# Blackberry_Trackballer_Breakout.net
KiCad netlist of a schematic drawn in EAGLE
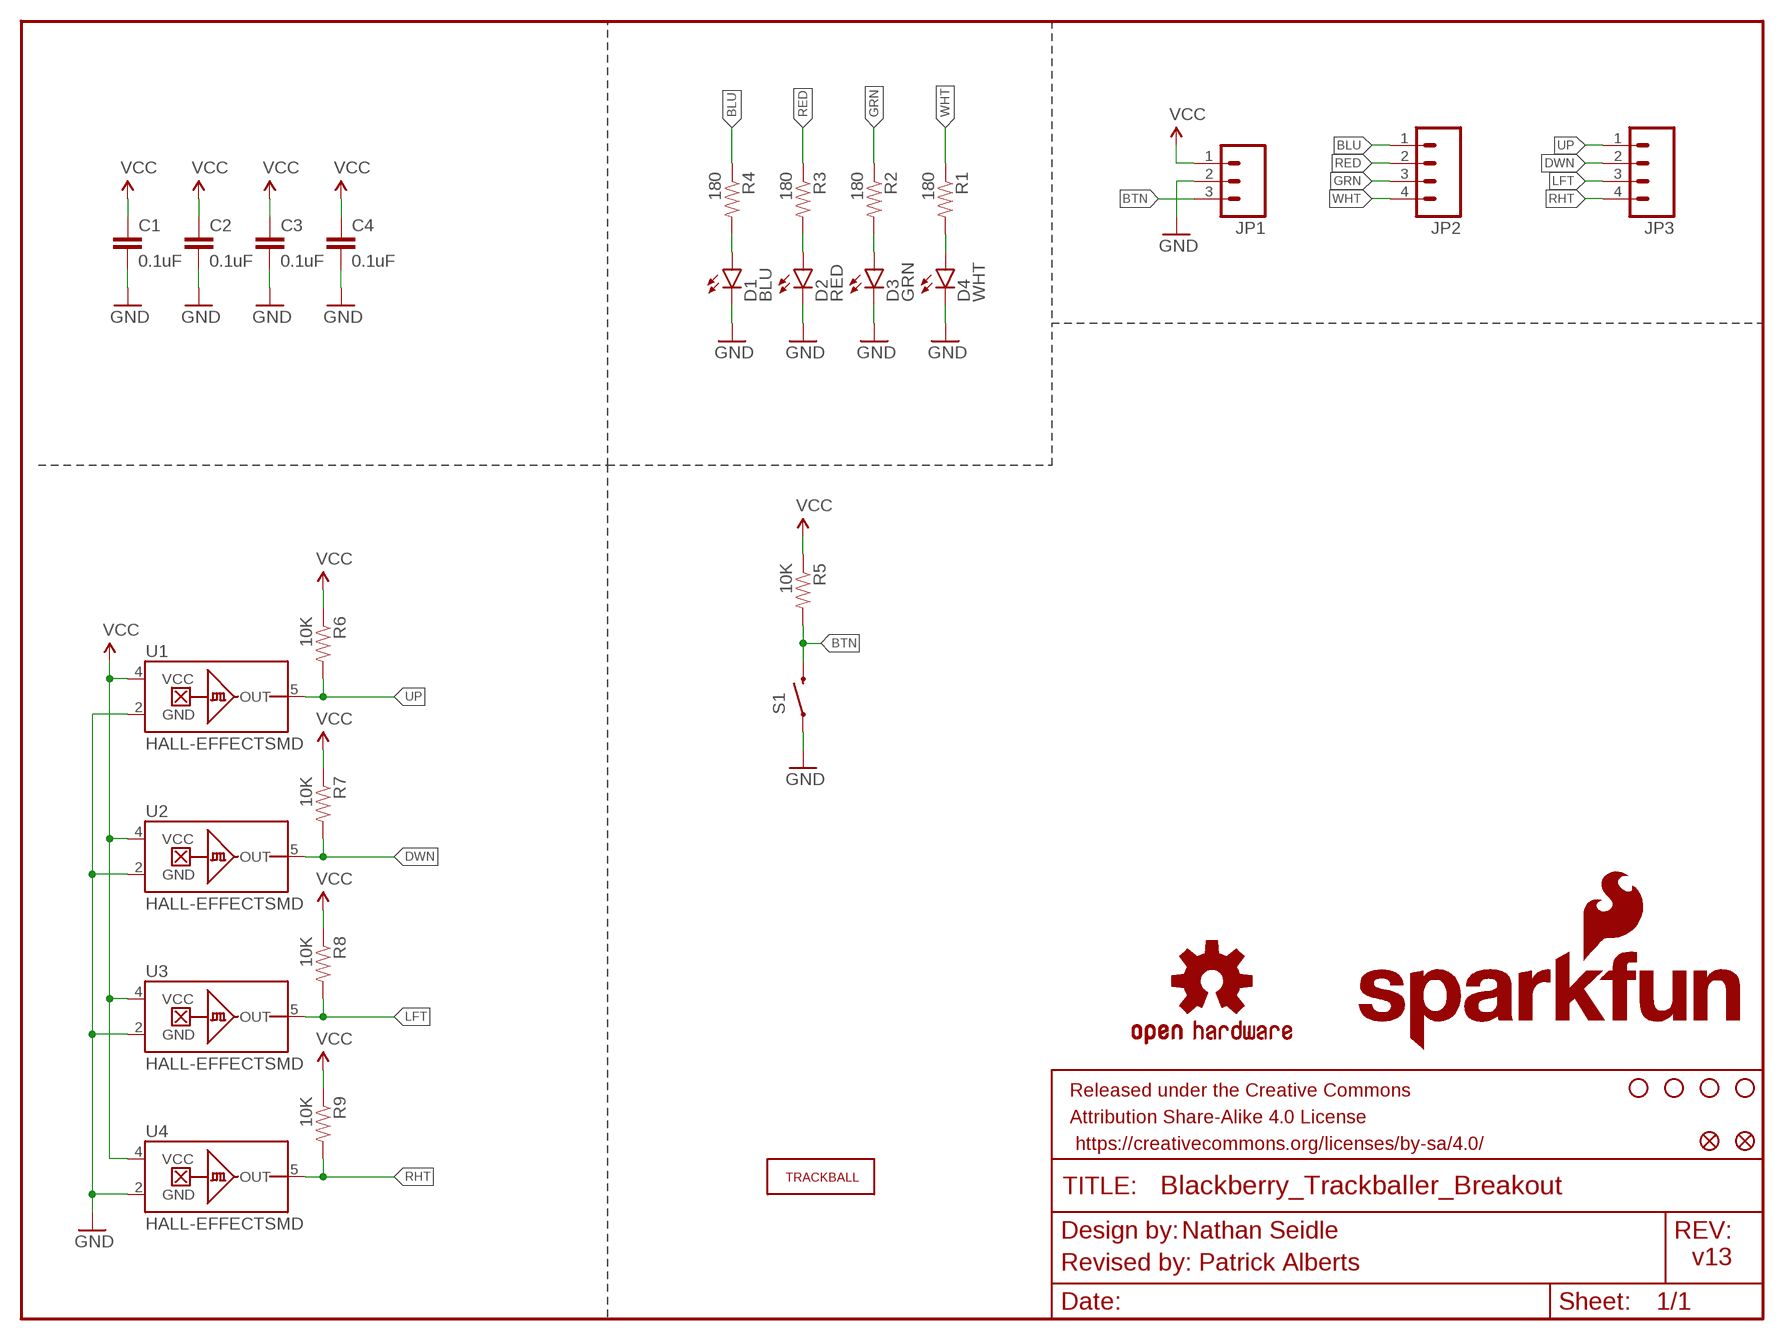
[diagram p0: schematic, sheet 1]

(export (version "E")
  (design (tool "Eeschema 10.0.6"))
  (components
    (comp (ref "C1")
      (value "0.1uF")
      (footprint "eagle-import:0603-CAP")
      (libsource (lib "eagle-import") (part "0.1UF-25V(+80/-20%)(0603)"))
    )
    (comp (ref "C2")
      (value "0.1uF")
      (footprint "eagle-import:0603-CAP")
      (libsource (lib "eagle-import") (part "0.1UF-25V(+80/-20%)(0603)"))
    )
    (comp (ref "C3")
      (value "0.1uF")
      (footprint "eagle-import:0603-CAP")
      (libsource (lib "eagle-import") (part "0.1UF-25V(+80/-20%)(0603)"))
    )
    (comp (ref "C4")
      (value "0.1uF")
      (footprint "eagle-import:0603-CAP")
      (libsource (lib "eagle-import") (part "0.1UF-25V(+80/-20%)(0603)"))
    )
    (comp (ref "D1")
      (value "BLU")
      (footprint "eagle-import:LED-0603")
      (libsource (lib "eagle-import") (part "LED-BLUE0603"))
    )
    (comp (ref "D2")
      (value "RED")
      (footprint "eagle-import:LED-0603")
      (libsource (lib "eagle-import") (part "LED-RED0603"))
    )
    (comp (ref "D3")
      (value "GRN")
      (footprint "eagle-import:LED-0603")
      (libsource (lib "eagle-import") (part "LED-GREEN0603"))
    )
    (comp (ref "D4")
      (value "WHT")
      (footprint "eagle-import:LED-0603")
      (libsource (lib "eagle-import") (part "LED-WHITE0603"))
    )
    (comp (ref "E$1")
      (value "FIDUCIAL1X2")
      (footprint "eagle-import:FIDUCIAL-1X2")
      (libsource (lib "eagle-import") (part "FIDUCIAL1X2"))
    )
    (comp (ref "E$2")
      (value "FIDUCIAL1X2")
      (footprint "eagle-import:FIDUCIAL-1X2")
      (libsource (lib "eagle-import") (part "FIDUCIAL1X2"))
    )
    (comp (ref "FRAME1")
      (value "FRAME-LETTER")
      (footprint "eagle-import:CREATIVE_COMMONS")
      (libsource (lib "eagle-import") (part "FRAME-LETTER"))
    )
    (comp (ref "JP1")
      (value "M03PTH")
      (footprint "eagle-import:1X03")
      (libsource (lib "eagle-import") (part "M03PTH"))
    )
    (comp (ref "JP2")
      (value "M04PTH")
      (footprint "eagle-import:1X04")
      (libsource (lib "eagle-import") (part "M04PTH"))
    )
    (comp (ref "JP3")
      (value "M04PTH")
      (footprint "eagle-import:1X04")
      (libsource (lib "eagle-import") (part "M04PTH"))
    )
    (comp (ref "LOGO1")
      (value "SFE_LOGO_NAME_FLAME.2_INCH")
      (footprint "eagle-import:SFE_LOGO_NAME_FLAME_.2")
      (libsource (lib "eagle-import") (part "SFE_LOGO_NAME_FLAME.2_INCH"))
    )
    (comp (ref "LOGO2")
      (value "OSHW-LOGOS")
      (footprint "eagle-import:OSHW-LOGO-S")
      (libsource (lib "eagle-import") (part "OSHW-LOGOS"))
    )
    (comp (ref "R1")
      (value "180")
      (footprint "eagle-import:0603-RES")
      (libsource (lib "eagle-import") (part "180OHM1/10W1%(0603)"))
    )
    (comp (ref "R2")
      (value "180")
      (footprint "eagle-import:0603-RES")
      (libsource (lib "eagle-import") (part "180OHM1/10W1%(0603)"))
    )
    (comp (ref "R3")
      (value "180")
      (footprint "eagle-import:0603-RES")
      (libsource (lib "eagle-import") (part "180OHM1/10W1%(0603)"))
    )
    (comp (ref "R4")
      (value "180")
      (footprint "eagle-import:0603-RES")
      (libsource (lib "eagle-import") (part "180OHM1/10W1%(0603)"))
    )
    (comp (ref "R5")
      (value "10K")
      (footprint "eagle-import:0603-RES")
      (libsource (lib "eagle-import") (part "10KOHM1/10W1%(0603)0603"))
    )
    (comp (ref "R6")
      (value "10K")
      (footprint "eagle-import:0603-RES")
      (libsource (lib "eagle-import") (part "10KOHM1/10W1%(0603)0603"))
    )
    (comp (ref "R7")
      (value "10K")
      (footprint "eagle-import:0603-RES")
      (libsource (lib "eagle-import") (part "10KOHM1/10W1%(0603)0603"))
    )
    (comp (ref "R8")
      (value "10K")
      (footprint "eagle-import:0603-RES")
      (libsource (lib "eagle-import") (part "10KOHM1/10W1%(0603)0603"))
    )
    (comp (ref "R9")
      (value "10K")
      (footprint "eagle-import:0603-RES")
      (libsource (lib "eagle-import") (part "10KOHM1/10W1%(0603)0603"))
    )
    (comp (ref "S1")
      (value "SWITCH-MOMENTARY-2SMD-2")
      (footprint "eagle-import:TACTILE_SWITCH_SMD-2")
      (libsource (lib "eagle-import") (part "SWITCH-MOMENTARY-2SMD-2"))
    )
    (comp (ref "U$1")
      (value "STAND-OFF")
      (footprint "eagle-import:STAND-OFF")
      (libsource (lib "eagle-import") (part "STAND-OFF"))
    )
    (comp (ref "U$3")
      (value "TRACKBALLMECH")
      (footprint "eagle-import:TRACKBALL")
      (libsource (lib "eagle-import") (part "TRACKBALLMECH"))
    )
    (comp (ref "U$8")
      (value "STAND-OFF")
      (footprint "eagle-import:STAND-OFF")
      (libsource (lib "eagle-import") (part "STAND-OFF"))
    )
    (comp (ref "U$11")
      (value "STAND-OFF")
      (footprint "eagle-import:STAND-OFF")
      (libsource (lib "eagle-import") (part "STAND-OFF"))
    )
    (comp (ref "U$14")
      (value "STAND-OFF")
      (footprint "eagle-import:STAND-OFF")
      (libsource (lib "eagle-import") (part "STAND-OFF"))
    )
    (comp (ref "U1")
      (value "HALL-EFFECTSMD")
      (footprint "eagle-import:SC70")
      (libsource (lib "eagle-import") (part "HALL-EFFECTSMD"))
    )
    (comp (ref "U2")
      (value "HALL-EFFECTSMD")
      (footprint "eagle-import:SC70")
      (libsource (lib "eagle-import") (part "HALL-EFFECTSMD"))
    )
    (comp (ref "U3")
      (value "HALL-EFFECTSMD")
      (footprint "eagle-import:SC70")
      (libsource (lib "eagle-import") (part "HALL-EFFECTSMD"))
    )
    (comp (ref "U4")
      (value "HALL-EFFECTSMD")
      (footprint "eagle-import:SC70")
      (libsource (lib "eagle-import") (part "HALL-EFFECTSMD"))
    )
  )
  (nets
    (net (code "1") (name "BLU") (class "Default")
      (node (ref "JP2") (pin "1") (pinfunction "1_1") (pintype "passive"))
      (node (ref "R4") (pin "1") (pinfunction "1_1") (pintype "passive"))
    )
    (net (code "2") (name "BTN") (class "Default")
      (node (ref "JP1") (pin "3") (pinfunction "3_3") (pintype "passive"))
      (node (ref "R5") (pin "2") (pinfunction "2_2") (pintype "passive"))
      (node (ref "S1") (pin "1") (pinfunction "2_1") (pintype "passive"))
    )
    (net (code "3") (name "DWN") (class "Default")
      (node (ref "JP3") (pin "2") (pinfunction "2_2") (pintype "passive"))
      (node (ref "R7") (pin "2") (pinfunction "2_2") (pintype "passive"))
      (node (ref "U2") (pin "5") (pinfunction "OUT_5") (pintype "bidirectional"))
    )
    (net (code "4") (name "GND") (class "Default")
      (node (ref "C1") (pin "2") (pinfunction "2_2") (pintype "passive"))
      (node (ref "C2") (pin "2") (pinfunction "2_2") (pintype "passive"))
      (node (ref "C3") (pin "2") (pinfunction "2_2") (pintype "passive"))
      (node (ref "C4") (pin "2") (pinfunction "2_2") (pintype "passive"))
      (node (ref "D1") (pin "C") (pinfunction "C_C") (pintype "passive"))
      (node (ref "D2") (pin "C") (pinfunction "C_C") (pintype "passive"))
      (node (ref "D3") (pin "C") (pinfunction "C_C") (pintype "passive"))
      (node (ref "D4") (pin "C") (pinfunction "C_C") (pintype "passive"))
      (node (ref "JP1") (pin "2") (pinfunction "2_2") (pintype "passive"))
      (node (ref "S1") (pin "2") (pinfunction "1_2") (pintype "passive"))
      (node (ref "U1") (pin "2") (pinfunction "GND_2") (pintype "bidirectional"))
      (node (ref "U2") (pin "2") (pinfunction "GND_2") (pintype "bidirectional"))
      (node (ref "U3") (pin "2") (pinfunction "GND_2") (pintype "bidirectional"))
      (node (ref "U4") (pin "2") (pinfunction "GND_2") (pintype "bidirectional"))
    )
    (net (code "5") (name "GRN") (class "Default")
      (node (ref "JP2") (pin "3") (pinfunction "3_3") (pintype "passive"))
      (node (ref "R2") (pin "1") (pinfunction "1_1") (pintype "passive"))
    )
    (net (code "6") (name "LFT") (class "Default")
      (node (ref "JP3") (pin "3") (pinfunction "3_3") (pintype "passive"))
      (node (ref "R8") (pin "2") (pinfunction "2_2") (pintype "passive"))
      (node (ref "U3") (pin "5") (pinfunction "OUT_5") (pintype "bidirectional"))
    )
    (net (code "7") (name "Net-(D1-PadA)") (class "Default")
      (node (ref "D1") (pin "A") (pinfunction "A_A") (pintype "passive"))
      (node (ref "R4") (pin "2") (pinfunction "2_2") (pintype "passive"))
    )
    (net (code "8") (name "Net-(D2-PadA)") (class "Default")
      (node (ref "D2") (pin "A") (pinfunction "A_A") (pintype "passive"))
      (node (ref "R3") (pin "2") (pinfunction "2_2") (pintype "passive"))
    )
    (net (code "9") (name "Net-(D3-PadA)") (class "Default")
      (node (ref "D3") (pin "A") (pinfunction "A_A") (pintype "passive"))
      (node (ref "R2") (pin "2") (pinfunction "2_2") (pintype "passive"))
    )
    (net (code "10") (name "Net-(D4-PadA)") (class "Default")
      (node (ref "D4") (pin "A") (pinfunction "A_A") (pintype "passive"))
      (node (ref "R1") (pin "2") (pinfunction "2_2") (pintype "passive"))
    )
    (net (code "11") (name "RED") (class "Default")
      (node (ref "JP2") (pin "2") (pinfunction "2_2") (pintype "passive"))
      (node (ref "R3") (pin "1") (pinfunction "1_1") (pintype "passive"))
    )
    (net (code "12") (name "RHT") (class "Default")
      (node (ref "JP3") (pin "4") (pinfunction "4_4") (pintype "passive"))
      (node (ref "R9") (pin "2") (pinfunction "2_2") (pintype "passive"))
      (node (ref "U4") (pin "5") (pinfunction "OUT_5") (pintype "bidirectional"))
    )
    (net (code "13") (name "UP") (class "Default")
      (node (ref "JP3") (pin "1") (pinfunction "1_1") (pintype "passive"))
      (node (ref "R6") (pin "2") (pinfunction "2_2") (pintype "passive"))
      (node (ref "U1") (pin "5") (pinfunction "OUT_5") (pintype "bidirectional"))
    )
    (net (code "14") (name "VCC") (class "Default")
      (node (ref "C1") (pin "1") (pinfunction "1_1") (pintype "passive"))
      (node (ref "C2") (pin "1") (pinfunction "1_1") (pintype "passive"))
      (node (ref "C3") (pin "1") (pinfunction "1_1") (pintype "passive"))
      (node (ref "C4") (pin "1") (pinfunction "1_1") (pintype "passive"))
      (node (ref "JP1") (pin "1") (pinfunction "1_1") (pintype "passive"))
      (node (ref "R5") (pin "1") (pinfunction "1_1") (pintype "passive"))
      (node (ref "R6") (pin "1") (pinfunction "1_1") (pintype "passive"))
      (node (ref "R7") (pin "1") (pinfunction "1_1") (pintype "passive"))
      (node (ref "R8") (pin "1") (pinfunction "1_1") (pintype "passive"))
      (node (ref "R9") (pin "1") (pinfunction "1_1") (pintype "passive"))
      (node (ref "U1") (pin "4") (pinfunction "VCC_4") (pintype "bidirectional"))
      (node (ref "U2") (pin "4") (pinfunction "VCC_4") (pintype "bidirectional"))
      (node (ref "U3") (pin "4") (pinfunction "VCC_4") (pintype "bidirectional"))
      (node (ref "U4") (pin "4") (pinfunction "VCC_4") (pintype "bidirectional"))
    )
    (net (code "15") (name "WHT") (class "Default")
      (node (ref "JP2") (pin "4") (pinfunction "4_4") (pintype "passive"))
      (node (ref "R1") (pin "1") (pinfunction "1_1") (pintype "passive"))
    )
  )
)
